# Sheet3-new.net
KiCad netlist of a schematic drawn in Altium Designer
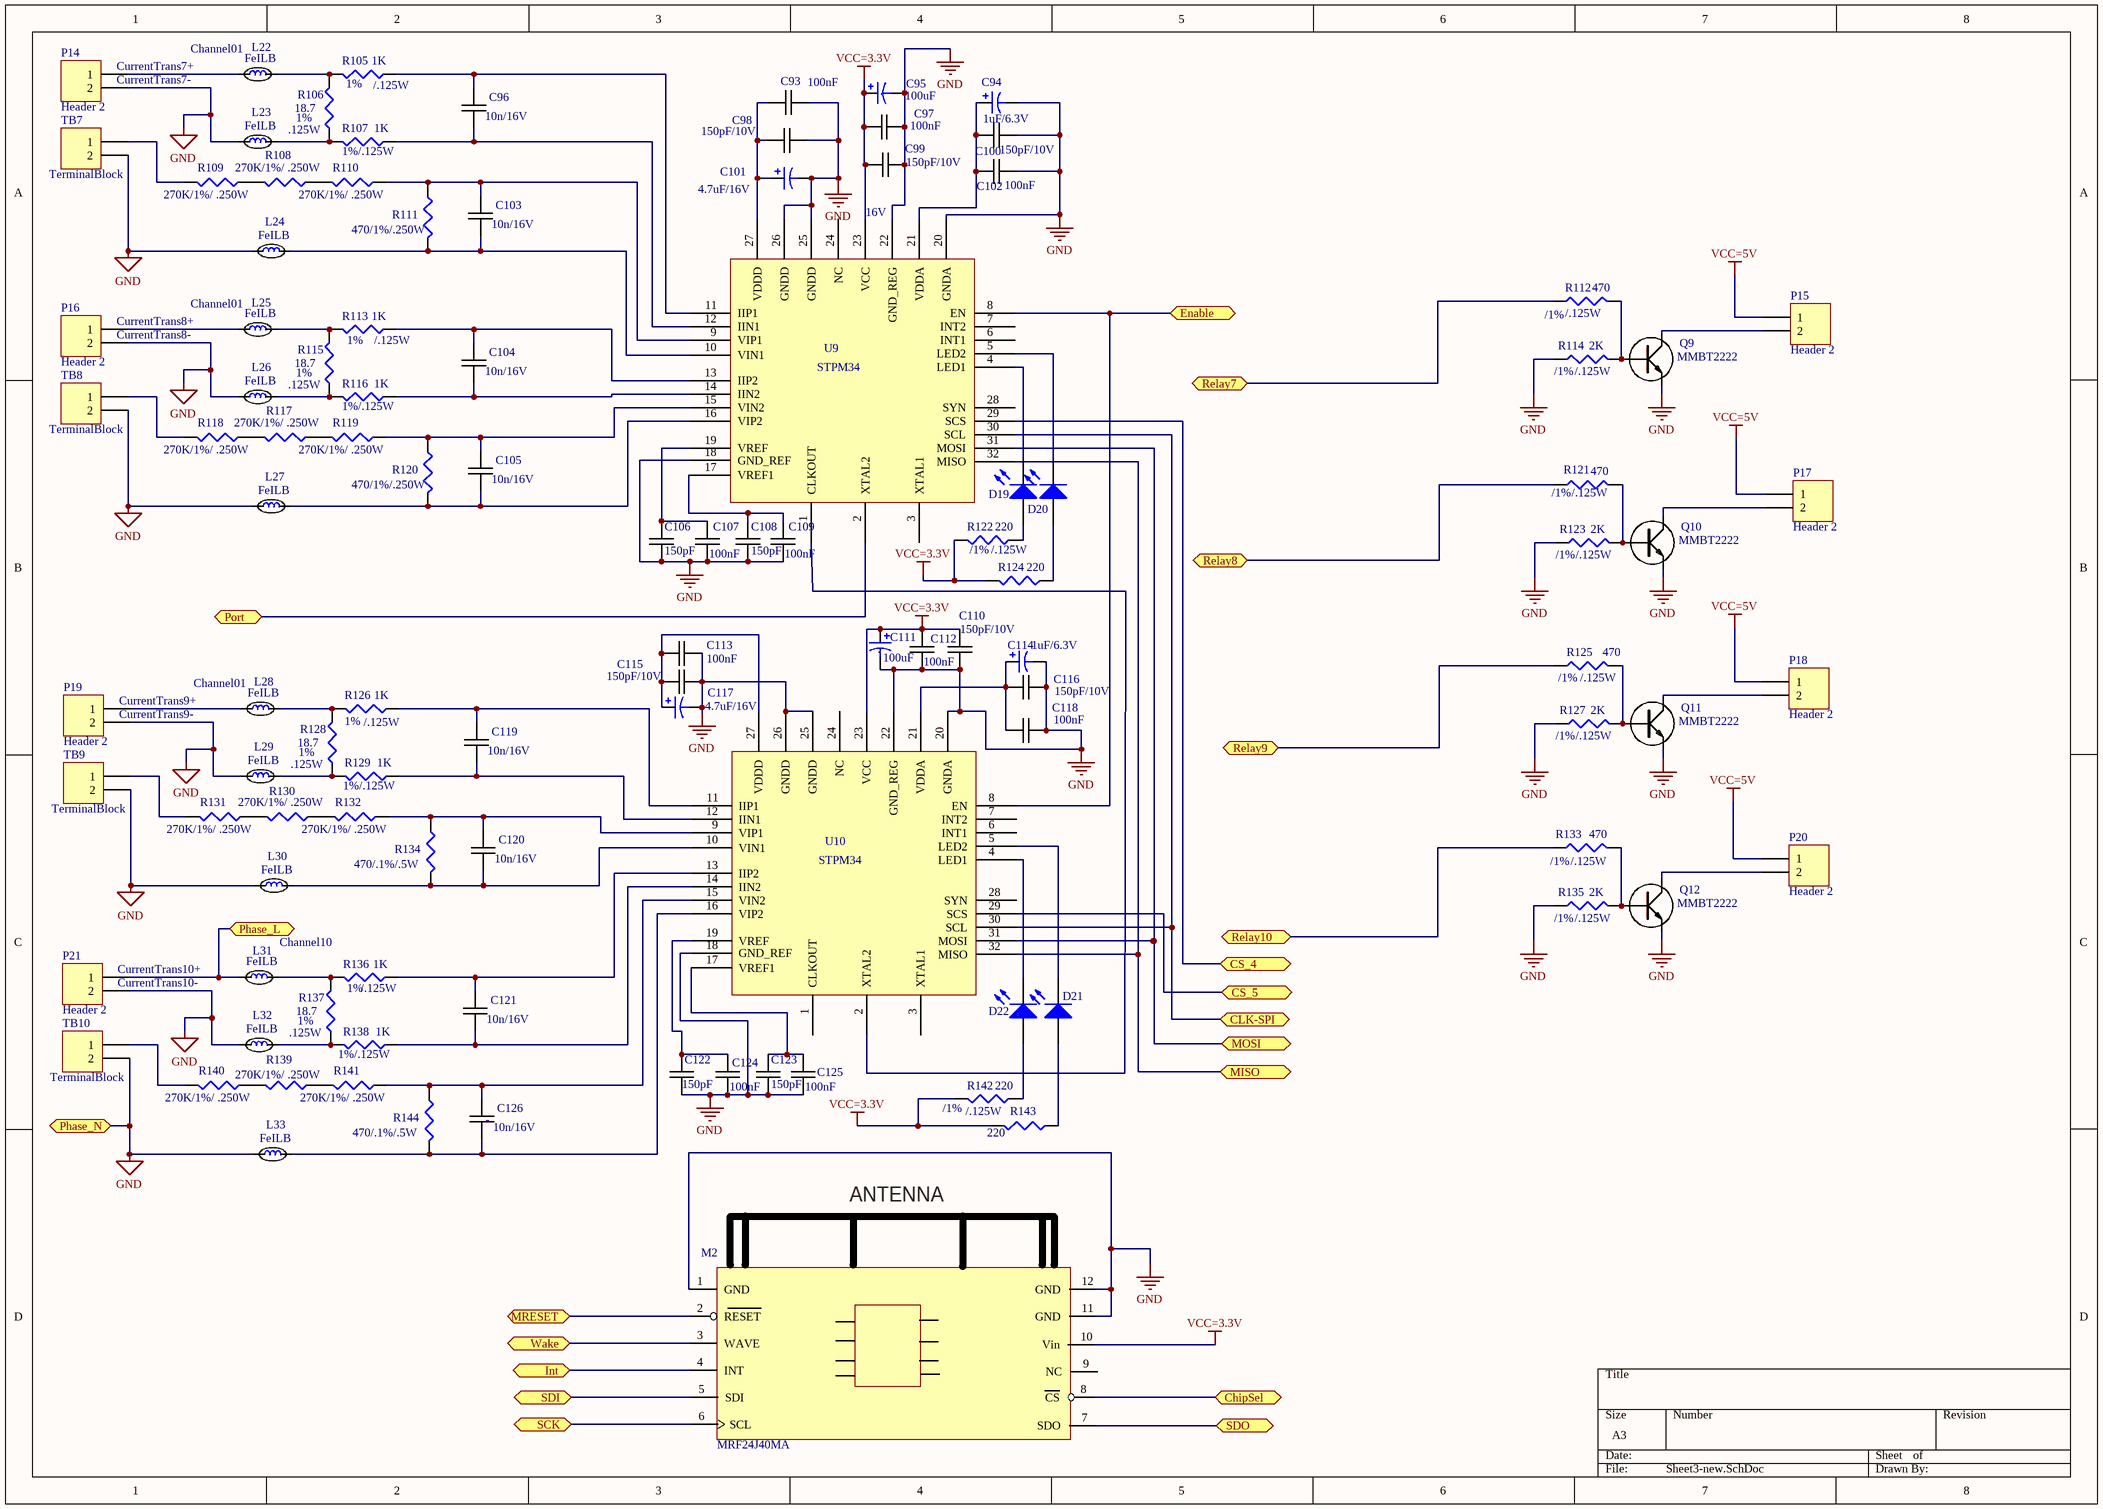
[diagram p0: Sheet3-new.SchDoc]

(export (version "E")
  (design (tool "Eeschema 10.0.6"))
  (components
    (comp (ref "C93")
      (value "100nF")
      (footprint "0402C-GENERIC")
      (description "CAPACITOR 0805 CERAMIC")
      (fields (field (name "MANUFACTURER") "Taiyo Yuden"))
      (libsource (lib "vh_altium_library") (part "0805C-18PF-50V-C0G-JOH"))
    )
    (comp (ref "C94")
      (value "1uF/6.3V")
      (footprint "0402C-GENERIC")
      (description "Polarized Capacitor (Surface Mount)")
      (fields (field (name "PUBLISHER") "Altium Limited"))
      (libsource (lib "Miscellaneous Devices") (part "Cap Pol3"))
    )
    (comp (ref "C95")
      (value "100uF")
      (footprint "100uF/10V")
      (description "Polarized Capacitor (Surface Mount)")
      (fields (field (name "MANUFACTURER") "Nichicon") (field (name "PUBLISHER") "Altium Limited"))
      (libsource (lib "Miscellaneous Devices") (part "Cap Pol3"))
    )
    (comp (ref "C96")
      (value "10n/16V")
      (footprint "0402C-GENERIC")
      (description "CAPACITOR 0805 CERAMIC")
      (fields (field (name "MANUFACTURER") "Murata Electronics"))
      (libsource (lib "vh_altium_library") (part "0805C-18PF-50V-C0G-JOH"))
    )
    (comp (ref "C97")
      (value "100nF")
      (footprint "0402C-GENERIC")
      (description "CAPACITOR 0805 CERAMIC")
      (fields (field (name "MANUFACTURER") "Taiyo Yuden"))
      (libsource (lib "vh_altium_library") (part "0805C-18PF-50V-C0G-JOH"))
    )
    (comp (ref "C98")
      (value "150pF/10V")
      (footprint "0402C-GENERIC")
      (description "CAPACITOR 0805 CERAMIC")
      (fields (field (name "MANUFACTURER") "Wurth Electronics"))
      (libsource (lib "vh_altium_library") (part "0805C-18PF-50V-C0G-JOH"))
    )
    (comp (ref "C99")
      (value "150pF/10V")
      (footprint "0402C-GENERIC")
      (description "CAPACITOR 0805 CERAMIC")
      (fields (field (name "MANUFACTURER") "Wurth Electronics"))
      (libsource (lib "vh_altium_library") (part "0805C-18PF-50V-C0G-JOH"))
    )
    (comp (ref "C100")
      (value "150pF/10V")
      (footprint "0402C-GENERIC")
      (description "CAPACITOR 0805 CERAMIC")
      (fields (field (name "MANUFACTURER") "Wurth Electronics"))
      (libsource (lib "vh_altium_library") (part "0805C-18PF-50V-C0G-JOH"))
    )
    (comp (ref "C101")
      (value "4.7uF/16V")
      (footprint "0805C-GENERIC")
      (description "Polarized Capacitor (Surface Mount)")
      (fields (field (name "MANUFACTURER") "Murata") (field (name "PUBLISHER") "Altium Limited"))
      (libsource (lib "Miscellaneous Devices") (part "Cap Pol3"))
    )
    (comp (ref "C102")
      (value "100nF")
      (footprint "0402C-GENERIC")
      (description "CAPACITOR 0805 CERAMIC")
      (fields (field (name "MANUFACTURER") "Taiyo Yuden"))
      (libsource (lib "vh_altium_library") (part "0805C-18PF-50V-C0G-JOH"))
    )
    (comp (ref "C103")
      (value "10n/16V")
      (footprint "0402C-GENERIC")
      (description "CAPACITOR 0805 CERAMIC")
      (fields (field (name "MANUFACTURER") "Murata Electronics"))
      (libsource (lib "vh_altium_library") (part "0805C-18PF-50V-C0G-JOH"))
    )
    (comp (ref "C104")
      (value "10n/16V")
      (footprint "0402C-GENERIC")
      (description "CAPACITOR 0805 CERAMIC")
      (fields (field (name "MANUFACTURER") "Murata Electronics"))
      (libsource (lib "vh_altium_library") (part "0805C-18PF-50V-C0G-JOH"))
    )
    (comp (ref "C105")
      (value "10n/16V")
      (footprint "0402C-GENERIC")
      (description "CAPACITOR 0805 CERAMIC")
      (fields (field (name "MANUFACTURER") "Murata Electronics"))
      (libsource (lib "vh_altium_library") (part "0805C-18PF-50V-C0G-JOH"))
    )
    (comp (ref "C106")
      (value "150pF")
      (footprint "0402C-GENERIC")
      (description "CAPACITOR 0805 CERAMIC")
      (fields (field (name "MANUFACTURER") "Wurth Electronics"))
      (libsource (lib "vh_altium_library") (part "0805C-18PF-50V-C0G-JOH"))
    )
    (comp (ref "C107")
      (value "100nF")
      (footprint "0402C-GENERIC")
      (description "CAPACITOR 0805 CERAMIC")
      (fields (field (name "MANUFACTURER") "Taiyo Yuden"))
      (libsource (lib "vh_altium_library") (part "0805C-18PF-50V-C0G-JOH"))
    )
    (comp (ref "C108")
      (value "150pF")
      (footprint "0402C-GENERIC")
      (description "CAPACITOR 0805 CERAMIC")
      (fields (field (name "MANUFACTURER") "Wurth Electronics"))
      (libsource (lib "vh_altium_library") (part "0805C-18PF-50V-C0G-JOH"))
    )
    (comp (ref "C109")
      (value "100nF")
      (footprint "0402C-GENERIC")
      (description "CAPACITOR 0805 CERAMIC")
      (fields (field (name "MANUFACTURER") "Taiyo Yuden"))
      (libsource (lib "vh_altium_library") (part "0805C-18PF-50V-C0G-JOH"))
    )
    (comp (ref "C110")
      (value "150pF/10V")
      (footprint "0402C-GENERIC")
      (description "CAPACITOR 0805 CERAMIC")
      (fields (field (name "MANUFACTURER") "Wurth Electronics"))
      (libsource (lib "vh_altium_library") (part "0805C-18PF-50V-C0G-JOH"))
    )
    (comp (ref "C111")
      (value "100uF")
      (footprint "100uF/10V")
      (description "Polarized Capacitor (Surface Mount)")
      (fields (field (name "MANUFACTURER") "Nichicon") (field (name "PUBLISHER") "Altium Limited"))
      (libsource (lib "Miscellaneous Devices") (part "Cap Pol3"))
    )
    (comp (ref "C112")
      (value "100nF")
      (footprint "0402C-GENERIC")
      (description "CAPACITOR 0805 CERAMIC")
      (fields (field (name "MANUFACTURER") "Taiyo Yuden"))
      (libsource (lib "vh_altium_library") (part "0805C-18PF-50V-C0G-JOH"))
    )
    (comp (ref "C113")
      (value "100nF")
      (footprint "0402C-GENERIC")
      (description "CAPACITOR 0805 CERAMIC")
      (fields (field (name "MANUFACTURER") "Taiyo Yuden"))
      (libsource (lib "vh_altium_library") (part "0805C-18PF-50V-C0G-JOH"))
    )
    (comp (ref "C114")
      (value "1uF/6.3V")
      (footprint "0402C-GENERIC")
      (description "Polarized Capacitor (Surface Mount)")
      (fields (field (name "PUBLISHER") "Altium Limited"))
      (libsource (lib "Miscellaneous Devices") (part "Cap Pol3"))
    )
    (comp (ref "C115")
      (value "150pF/10V")
      (footprint "0402C-GENERIC")
      (description "CAPACITOR 0805 CERAMIC")
      (fields (field (name "MANUFACTURER") "Wurth Electronics"))
      (libsource (lib "vh_altium_library") (part "0805C-18PF-50V-C0G-JOH"))
    )
    (comp (ref "C116")
      (value "150pF/10V")
      (footprint "0402C-GENERIC")
      (description "CAPACITOR 0805 CERAMIC")
      (fields (field (name "MANUFACTURER") "Wurth Electronics"))
      (libsource (lib "vh_altium_library") (part "0805C-18PF-50V-C0G-JOH"))
    )
    (comp (ref "C117")
      (value "4.7uF/16V")
      (footprint "0805C-GENERIC")
      (description "Polarized Capacitor (Surface Mount)")
      (fields (field (name "MANUFACTURER") "Murata") (field (name "PUBLISHER") "Altium Limited"))
      (libsource (lib "Miscellaneous Devices") (part "Cap Pol3"))
    )
    (comp (ref "C118")
      (value "100nF")
      (footprint "0402C-GENERIC")
      (description "CAPACITOR 0805 CERAMIC")
      (fields (field (name "MANUFACTURER") "Taiyo Yuden"))
      (libsource (lib "vh_altium_library") (part "0805C-18PF-50V-C0G-JOH"))
    )
    (comp (ref "C119")
      (value "10n/16V")
      (footprint "0402C-GENERIC")
      (description "CAPACITOR 0805 CERAMIC")
      (fields (field (name "MANUFACTURER") "Murata Electronics"))
      (libsource (lib "vh_altium_library") (part "0805C-18PF-50V-C0G-JOH"))
    )
    (comp (ref "C120")
      (value "10n/16V")
      (footprint "0402C-GENERIC")
      (description "CAPACITOR 0805 CERAMIC")
      (fields (field (name "MANUFACTURER") "Murata Electronics"))
      (libsource (lib "vh_altium_library") (part "0805C-18PF-50V-C0G-JOH"))
    )
    (comp (ref "C121")
      (value "10n/16V")
      (footprint "0402C-GENERIC")
      (description "CAPACITOR 0805 CERAMIC")
      (fields (field (name "MANUFACTURER") "Murata Electronics"))
      (libsource (lib "vh_altium_library") (part "0805C-18PF-50V-C0G-JOH"))
    )
    (comp (ref "C122")
      (value "150pF")
      (footprint "0402C-GENERIC")
      (description "CAPACITOR 0805 CERAMIC")
      (fields (field (name "MANUFACTURER") "Wurth Electronics"))
      (libsource (lib "vh_altium_library") (part "0805C-18PF-50V-C0G-JOH"))
    )
    (comp (ref "C123")
      (value "150pF")
      (footprint "0402C-GENERIC")
      (description "CAPACITOR 0805 CERAMIC")
      (fields (field (name "MANUFACTURER") "Wurth Electronics"))
      (libsource (lib "vh_altium_library") (part "0805C-18PF-50V-C0G-JOH"))
    )
    (comp (ref "C124")
      (value "100nF")
      (footprint "0402C-GENERIC")
      (description "CAPACITOR 0805 CERAMIC")
      (fields (field (name "MANUFACTURER") "Taiyo Yuden"))
      (libsource (lib "vh_altium_library") (part "0805C-18PF-50V-C0G-JOH"))
    )
    (comp (ref "C125")
      (value "100nF")
      (footprint "0402C-GENERIC")
      (description "CAPACITOR 0805 CERAMIC")
      (fields (field (name "MANUFACTURER") "Taiyo Yuden"))
      (libsource (lib "vh_altium_library") (part "0805C-18PF-50V-C0G-JOH"))
    )
    (comp (ref "C126")
      (value "10n/16V")
      (footprint "0402C-GENERIC")
      (description "CAPACITOR 0805 CERAMIC")
      (fields (field (name "MANUFACTURER") "Murata Electronics"))
      (libsource (lib "vh_altium_library") (part "0805C-18PF-50V-C0G-JOH"))
    )
    (comp (ref "D19")
      (value "LED2")
      (footprint "LED-SM")
      (description "Typical RED, GREEN, YELLOW, AMBER GaAs LED")
      (fields (field (name "MANUFACTURER") "Lite-On Inc") (field (name "PUBLISHER") "Altium Limited"))
      (libsource (lib "Miscellaneous Devices") (part "LED2"))
    )
    (comp (ref "D20")
      (value "LED2")
      (footprint "LED-SM")
      (description "Typical RED, GREEN, YELLOW, AMBER GaAs LED")
      (fields (field (name "MANUFACTURER") "Lite-On Inc") (field (name "PUBLISHER") "Altium Limited"))
      (libsource (lib "Miscellaneous Devices") (part "LED2"))
    )
    (comp (ref "D21")
      (value "LED2")
      (footprint "LED-SM")
      (description "Typical RED, GREEN, YELLOW, AMBER GaAs LED")
      (fields (field (name "MANUFACTURER") "Lite-On Inc") (field (name "PUBLISHER") "Altium Limited"))
      (libsource (lib "Miscellaneous Devices") (part "LED2"))
    )
    (comp (ref "D22")
      (value "LED2")
      (footprint "LED-SM")
      (description "Typical RED, GREEN, YELLOW, AMBER GaAs LED")
      (fields (field (name "MANUFACTURER") "Lite-On Inc") (field (name "PUBLISHER") "Altium Limited"))
      (libsource (lib "Miscellaneous Devices") (part "LED2"))
    )
    (comp (ref "L22")
      (value "FeILB")
      (footprint "0603C-TBD")
      (fields (field (name "MANUFACTURER") "Brand Samsung"))
      (libsource (lib "SMLib") (part "FerrBeads/ILBB"))
    )
    (comp (ref "L23")
      (value "FeILB")
      (footprint "0603C-TBD")
      (fields (field (name "MANUFACTURER") "Brand Samsung"))
      (libsource (lib "SMLib") (part "FerrBeads/ILBB"))
    )
    (comp (ref "L24")
      (value "FeILB")
      (footprint "0603C-TBD")
      (fields (field (name "MANUFACTURER") "Brand Samsung"))
      (libsource (lib "SMLib") (part "FerrBeads/ILBB"))
    )
    (comp (ref "L25")
      (value "FeILB")
      (footprint "0603C-TBD")
      (fields (field (name "MANUFACTURER") "Brand Samsung"))
      (libsource (lib "SMLib") (part "FerrBeads/ILBB"))
    )
    (comp (ref "L26")
      (value "FeILB")
      (footprint "0603C-TBD")
      (fields (field (name "MANUFACTURER") "Brand Samsung"))
      (libsource (lib "SMLib") (part "FerrBeads/ILBB"))
    )
    (comp (ref "L27")
      (value "FeILB")
      (footprint "0603C-TBD")
      (fields (field (name "MANUFACTURER") "Brand Samsung"))
      (libsource (lib "SMLib") (part "FerrBeads/ILBB"))
    )
    (comp (ref "L28")
      (value "FeILB")
      (footprint "0603C-TBD")
      (fields (field (name "MANUFACTURER") "Brand Samsung"))
      (libsource (lib "SMLib") (part "FerrBeads/ILBB"))
    )
    (comp (ref "L29")
      (value "FeILB")
      (footprint "0603C-TBD")
      (fields (field (name "MANUFACTURER") "Brand Samsung"))
      (libsource (lib "SMLib") (part "FerrBeads/ILBB"))
    )
    (comp (ref "L30")
      (value "FeILB")
      (footprint "0603C-TBD")
      (fields (field (name "MANUFACTURER") "Brand Samsung"))
      (libsource (lib "SMLib") (part "FerrBeads/ILBB"))
    )
    (comp (ref "L31")
      (value "FeILB")
      (footprint "0603C-TBD")
      (fields (field (name "MANUFACTURER") "Brand Samsung"))
      (libsource (lib "SMLib") (part "FerrBeads/ILBB"))
    )
    (comp (ref "L32")
      (value "FeILB")
      (footprint "0603C-TBD")
      (fields (field (name "MANUFACTURER") "Brand Samsung"))
      (libsource (lib "SMLib") (part "FerrBeads/ILBB"))
    )
    (comp (ref "L33")
      (value "FeILB")
      (footprint "0603C-TBD")
      (fields (field (name "MANUFACTURER") "Brand Samsung"))
      (libsource (lib "SMLib") (part "FerrBeads/ILBB"))
    )
    (comp (ref "M2")
      (value "MRF24J40MA")
      (footprint "MRF24J40MA-zigBEE module")
      (fields (field (name "MANUFACTURER") "Microchip"))
      (libsource (lib "SMLib") (part "MRF24J40MA"))
    )
    (comp (ref "P14")
      (value "Header 2")
      (footprint "BG090-header")
      (description "Header, 2-Pin")
      (fields
        (field (name "MANUFACTURER") "Clobal Connector technology Ltd")
        (field (name "PUBLISHER") "Altium Limited")
      )
      (libsource (lib "Miscellaneous Connectors") (part "Header 2"))
    )
    (comp (ref "P15")
      (value "Header 2")
      (footprint "BG090-header")
      (description "Header, 2-Pin")
      (fields
        (field (name "MANUFACTURER") "Clobal Connector technology Ltd")
        (field (name "PUBLISHER") "Altium Limited")
      )
      (libsource (lib "") (part "Header 2_1"))
    )
    (comp (ref "P16")
      (value "Header 2")
      (footprint "BG090-header")
      (description "Header, 2-Pin")
      (fields
        (field (name "MANUFACTURER") "Clobal Connector technology Ltd")
        (field (name "PUBLISHER") "Altium Limited")
      )
      (libsource (lib "Miscellaneous Connectors") (part "Header 2"))
    )
    (comp (ref "P17")
      (value "Header 2")
      (footprint "BG090-header")
      (description "Header, 2-Pin")
      (fields
        (field (name "MANUFACTURER") "Clobal Connector technology Ltd")
        (field (name "PUBLISHER") "Altium Limited")
      )
      (libsource (lib "") (part "Header 2_1"))
    )
    (comp (ref "P18")
      (value "Header 2")
      (footprint "BG090-header")
      (description "Header, 2-Pin")
      (fields
        (field (name "MANUFACTURER") "Clobal Connector technology Ltd")
        (field (name "PUBLISHER") "Altium Limited")
      )
      (libsource (lib "") (part "Header 2_1"))
    )
    (comp (ref "P19")
      (value "Header 2")
      (footprint "BG090-header")
      (description "Header, 2-Pin")
      (fields
        (field (name "MANUFACTURER") "Clobal Connector technology Ltd")
        (field (name "PUBLISHER") "Altium Limited")
      )
      (libsource (lib "Miscellaneous Connectors") (part "Header 2"))
    )
    (comp (ref "P20")
      (value "Header 2")
      (footprint "BG090-header")
      (description "Header, 2-Pin")
      (fields
        (field (name "MANUFACTURER") "Clobal Connector technology Ltd")
        (field (name "PUBLISHER") "Altium Limited")
      )
      (libsource (lib "") (part "Header 2_1"))
    )
    (comp (ref "P21")
      (value "Header 2")
      (footprint "BG090-header")
      (description "Header, 2-Pin")
      (fields
        (field (name "MANUFACTURER") "Clobal Connector technology Ltd")
        (field (name "PUBLISHER") "Altium Limited")
      )
      (libsource (lib "Miscellaneous Connectors") (part "Header 2"))
    )
    (comp (ref "Q9")
      (value "MMBT2222")
      (footprint "MMBT2222")
      (description "BC847 SMALL SIGNAL NPN TRANSISTOR")
      (fields (field (name "MANUFACTURER") "Diodes  Inc."))
      (libsource (lib "vh_altium_library") (part "MMBT2222"))
    )
    (comp (ref "Q10")
      (value "MMBT2222")
      (footprint "MMBT2222")
      (description "BC847 SMALL SIGNAL NPN TRANSISTOR")
      (fields (field (name "MANUFACTURER") "Diodes  Inc."))
      (libsource (lib "vh_altium_library") (part "MMBT2222"))
    )
    (comp (ref "Q11")
      (value "MMBT2222")
      (footprint "MMBT2222")
      (description "BC847 SMALL SIGNAL NPN TRANSISTOR")
      (fields (field (name "MANUFACTURER") "Diodes  Inc."))
      (libsource (lib "vh_altium_library") (part "MMBT2222"))
    )
    (comp (ref "Q12")
      (value "MMBT2222")
      (footprint "MMBT2222")
      (description "BC847 SMALL SIGNAL NPN TRANSISTOR")
      (fields (field (name "MANUFACTURER") "Diodes  Inc."))
      (libsource (lib "vh_altium_library") (part "MMBT2222"))
    )
    (comp (ref "R105")
      (value "1K")
      (footprint "0805C-GENERIC")
      (description "Resistor")
      (fields
        (field (name "MANUFACTURER") "StackpoleElectronics")
        (field (name "PUBLISHER") "Altium Limited")
      )
      (libsource (lib "Miscellaneous Devices") (part "Res3"))
    )
    (comp (ref "R106")
      (value "18.7")
      (footprint "vh_altium_library:0805R-10")
      (description "Resistor")
      (fields (field (name "MANUFACTURER") "Vishay Pale") (field (name "PUBLISHER") "Altium Limited"))
      (libsource (lib "Miscellaneous Devices") (part "Res3"))
    )
    (comp (ref "R107")
      (value "1K")
      (footprint "0805C-GENERIC")
      (description "Resistor")
      (fields
        (field (name "MANUFACTURER") "StackpoleElectronics")
        (field (name "PUBLISHER") "Altium Limited")
      )
      (libsource (lib "Miscellaneous Devices") (part "Res3"))
    )
    (comp (ref "R108")
      (value "270K/1%/ .250W")
      (footprint "generic:1210R-GENERIC")
      (description "Resistor")
      (fields (field (name "MANUFACTURER") "Panasonic  Co") (field (name "PUBLISHER") "Altium Limited"))
      (libsource (lib "Miscellaneous Devices") (part "Res3"))
    )
    (comp (ref "R109")
      (value "270K/1%/ .250W")
      (footprint "generic:1210R-GENERIC")
      (description "Resistor")
      (fields (field (name "MANUFACTURER") "Panasonic  Co") (field (name "PUBLISHER") "Altium Limited"))
      (libsource (lib "Miscellaneous Devices") (part "Res3"))
    )
    (comp (ref "R110")
      (value "270K/1%/ .250W")
      (footprint "generic:1210R-GENERIC")
      (description "Resistor")
      (fields (field (name "MANUFACTURER") "Panasonic  Co") (field (name "PUBLISHER") "Altium Limited"))
      (libsource (lib "Miscellaneous Devices") (part "Res3"))
    )
    (comp (ref "R111")
      (value "470/1%/.250W")
      (footprint "1206FB-GENERIC")
      (description "Resistor")
      (fields (field (name "MANUFACTURER") "Panasonic Co") (field (name "PUBLISHER") "Altium Limited"))
      (libsource (lib "Miscellaneous Devices") (part "Res3"))
    )
    (comp (ref "R112")
      (value "470")
      (footprint "vh_altium_library:0805R-39")
      (description "Resistor")
      (fields
        (field (name "MANUFACTURER") "Stackpole electronics")
        (field (name "PUBLISHER") "Altium Limited")
      )
      (libsource (lib "Miscellaneous Devices") (part "Res3"))
    )
    (comp (ref "R113")
      (value "1K")
      (footprint "0805C-GENERIC")
      (description "Resistor")
      (fields
        (field (name "MANUFACTURER") "StackpoleElectronics")
        (field (name "PUBLISHER") "Altium Limited")
      )
      (libsource (lib "Miscellaneous Devices") (part "Res3"))
    )
    (comp (ref "R114")
      (value "2K")
      (footprint "vh_altium_library:0805R-180")
      (description "Resistor")
      (fields
        (field (name "MANUFACTURER") "Stackpole Electronics")
        (field (name "PUBLISHER") "Altium Limited")
      )
      (libsource (lib "Miscellaneous Devices") (part "Res3"))
    )
    (comp (ref "R115")
      (value "18.7")
      (footprint "vh_altium_library:0805R-10")
      (description "Resistor")
      (fields (field (name "MANUFACTURER") "Vishay Pale") (field (name "PUBLISHER") "Altium Limited"))
      (libsource (lib "Miscellaneous Devices") (part "Res3"))
    )
    (comp (ref "R116")
      (value "1K")
      (footprint "0805C-GENERIC")
      (description "Resistor")
      (fields
        (field (name "MANUFACTURER") "StackpoleElectronics")
        (field (name "PUBLISHER") "Altium Limited")
      )
      (libsource (lib "Miscellaneous Devices") (part "Res3"))
    )
    (comp (ref "R117")
      (value "270K/1%/ .250W")
      (footprint "generic:1210R-GENERIC")
      (description "Resistor")
      (fields (field (name "MANUFACTURER") "Panasonic  Co") (field (name "PUBLISHER") "Altium Limited"))
      (libsource (lib "Miscellaneous Devices") (part "Res3"))
    )
    (comp (ref "R118")
      (value "270K/1%/ .250W")
      (footprint "generic:1210R-GENERIC")
      (description "Resistor")
      (fields (field (name "MANUFACTURER") "Panasonic  Co") (field (name "PUBLISHER") "Altium Limited"))
      (libsource (lib "Miscellaneous Devices") (part "Res3"))
    )
    (comp (ref "R119")
      (value "270K/1%/ .250W")
      (footprint "generic:1210R-GENERIC")
      (description "Resistor")
      (fields (field (name "MANUFACTURER") "Panasonic  Co") (field (name "PUBLISHER") "Altium Limited"))
      (libsource (lib "Miscellaneous Devices") (part "Res3"))
    )
    (comp (ref "R120")
      (value "470/1%/.250W")
      (footprint "1206FB-GENERIC")
      (description "Resistor")
      (fields (field (name "MANUFACTURER") "Panasonic Co") (field (name "PUBLISHER") "Altium Limited"))
      (libsource (lib "Miscellaneous Devices") (part "Res3"))
    )
    (comp (ref "R121")
      (value "470")
      (footprint "vh_altium_library:0805R-39")
      (description "Resistor")
      (fields
        (field (name "MANUFACTURER") "Stackpole electronics")
        (field (name "PUBLISHER") "Altium Limited")
      )
      (libsource (lib "Miscellaneous Devices") (part "Res3"))
    )
    (comp (ref "R122")
      (value "220")
      (footprint "0805C-GENERIC")
      (description "Resistor")
      (fields
        (field (name "MANUFACTURER") "Stackpole Electronics")
        (field (name "PUBLISHER") "Altium Limited")
      )
      (libsource (lib "Miscellaneous Devices") (part "Res3"))
    )
    (comp (ref "R123")
      (value "2K")
      (footprint "vh_altium_library:0805R-180")
      (description "Resistor")
      (fields
        (field (name "MANUFACTURER") "Stackpole Electronics")
        (field (name "PUBLISHER") "Altium Limited")
      )
      (libsource (lib "Miscellaneous Devices") (part "Res3"))
    )
    (comp (ref "R124")
      (value "220")
      (footprint "0805C-GENERIC")
      (description "Resistor")
      (fields
        (field (name "MANUFACTURER") "Stackpole Electronics")
        (field (name "PUBLISHER") "Altium Limited")
      )
      (libsource (lib "Miscellaneous Devices") (part "Res3"))
    )
    (comp (ref "R125")
      (value "470")
      (footprint "vh_altium_library:0805R-39")
      (description "Resistor")
      (fields
        (field (name "MANUFACTURER") "Stackpole electronics")
        (field (name "PUBLISHER") "Altium Limited")
      )
      (libsource (lib "Miscellaneous Devices") (part "Res3"))
    )
    (comp (ref "R126")
      (value "1K")
      (footprint "0805C-GENERIC")
      (description "Resistor")
      (fields
        (field (name "MANUFACTURER") "StackpoleElectronics")
        (field (name "PUBLISHER") "Altium Limited")
      )
      (libsource (lib "Miscellaneous Devices") (part "Res3"))
    )
    (comp (ref "R127")
      (value "2K")
      (footprint "vh_altium_library:0805R-180")
      (description "Resistor")
      (fields
        (field (name "MANUFACTURER") "Stackpole Electronics")
        (field (name "PUBLISHER") "Altium Limited")
      )
      (libsource (lib "Miscellaneous Devices") (part "Res3"))
    )
    (comp (ref "R128")
      (value "18.7")
      (footprint "vh_altium_library:0805R-10")
      (description "Resistor")
      (fields (field (name "MANUFACTURER") "Vishay Pale") (field (name "PUBLISHER") "Altium Limited"))
      (libsource (lib "Miscellaneous Devices") (part "Res3"))
    )
    (comp (ref "R129")
      (value "1K")
      (footprint "0805C-GENERIC")
      (description "Resistor")
      (fields
        (field (name "MANUFACTURER") "StackpoleElectronics")
        (field (name "PUBLISHER") "Altium Limited")
      )
      (libsource (lib "Miscellaneous Devices") (part "Res3"))
    )
    (comp (ref "R130")
      (value "270K/1%/ .250W")
      (footprint "generic:1210R-GENERIC")
      (description "Resistor")
      (fields (field (name "MANUFACTURER") "Panasonic  Co") (field (name "PUBLISHER") "Altium Limited"))
      (libsource (lib "Miscellaneous Devices") (part "Res3"))
    )
    (comp (ref "R131")
      (value "270K/1%/ .250W")
      (footprint "generic:1210R-GENERIC")
      (description "Resistor")
      (fields (field (name "MANUFACTURER") "Panasonic  Co") (field (name "PUBLISHER") "Altium Limited"))
      (libsource (lib "Miscellaneous Devices") (part "Res3"))
    )
    (comp (ref "R132")
      (value "270K/1%/ .250W")
      (footprint "generic:1210R-GENERIC")
      (description "Resistor")
      (fields (field (name "MANUFACTURER") "Panasonic  Co") (field (name "PUBLISHER") "Altium Limited"))
      (libsource (lib "Miscellaneous Devices") (part "Res3"))
    )
    (comp (ref "R133")
      (value "470")
      (footprint "vh_altium_library:0805R-39")
      (description "Resistor")
      (fields
        (field (name "MANUFACTURER") "Stackpole electronics")
        (field (name "PUBLISHER") "Altium Limited")
      )
      (libsource (lib "Miscellaneous Devices") (part "Res3"))
    )
    (comp (ref "R134")
      (value "470/.1%/.5W")
      (footprint "1210C-GENERIC")
      (description "Resistor")
      (fields (field (name "MANUFACTURER") "Panasonic Co") (field (name "PUBLISHER") "Altium Limited"))
      (libsource (lib "Miscellaneous Devices") (part "Res3"))
    )
    (comp (ref "R135")
      (value "2K")
      (footprint "vh_altium_library:0805R-180")
      (description "Resistor")
      (fields
        (field (name "MANUFACTURER") "Stackpole Electronics")
        (field (name "PUBLISHER") "Altium Limited")
      )
      (libsource (lib "Miscellaneous Devices") (part "Res3"))
    )
    (comp (ref "R136")
      (value "1K")
      (footprint "0805C-GENERIC")
      (description "Resistor")
      (fields
        (field (name "MANUFACTURER") "StackpoleElectronics")
        (field (name "PUBLISHER") "Altium Limited")
      )
      (libsource (lib "Miscellaneous Devices") (part "Res3"))
    )
    (comp (ref "R137")
      (value "18.7")
      (footprint "vh_altium_library:0805R-10")
      (description "Resistor")
      (fields (field (name "MANUFACTURER") "Vishay Pale") (field (name "PUBLISHER") "Altium Limited"))
      (libsource (lib "Miscellaneous Devices") (part "Res3"))
    )
    (comp (ref "R138")
      (value "1K")
      (footprint "0805C-GENERIC")
      (description "Resistor")
      (fields
        (field (name "MANUFACTURER") "StackpoleElectronics")
        (field (name "PUBLISHER") "Altium Limited")
      )
      (libsource (lib "Miscellaneous Devices") (part "Res3"))
    )
    (comp (ref "R139")
      (value "270K/1%/ .250W")
      (footprint "generic:1210R-GENERIC")
      (description "Resistor")
      (fields (field (name "MANUFACTURER") "Panasonic  Co") (field (name "PUBLISHER") "Altium Limited"))
      (libsource (lib "Miscellaneous Devices") (part "Res3"))
    )
    (comp (ref "R140")
      (value "270K/1%/ .250W")
      (footprint "generic:1210R-GENERIC")
      (description "Resistor")
      (fields (field (name "MANUFACTURER") "Panasonic  Co") (field (name "PUBLISHER") "Altium Limited"))
      (libsource (lib "Miscellaneous Devices") (part "Res3"))
    )
    (comp (ref "R141")
      (value "270K/1%/ .250W")
      (footprint "generic:1210R-GENERIC")
      (description "Resistor")
      (fields (field (name "MANUFACTURER") "Panasonic  Co") (field (name "PUBLISHER") "Altium Limited"))
      (libsource (lib "Miscellaneous Devices") (part "Res3"))
    )
    (comp (ref "R142")
      (value "220")
      (footprint "0805C-GENERIC")
      (description "Resistor")
      (fields
        (field (name "MANUFACTURER") "Stackpole Electronics")
        (field (name "PUBLISHER") "Altium Limited")
      )
      (libsource (lib "Miscellaneous Devices") (part "Res3"))
    )
    (comp (ref "R143")
      (value "220")
      (footprint "0805C-GENERIC")
      (description "Resistor")
      (fields
        (field (name "MANUFACTURER") "Stackpole Electronics")
        (field (name "PUBLISHER") "Altium Limited")
      )
      (libsource (lib "Miscellaneous Devices") (part "Res3"))
    )
    (comp (ref "R144")
      (value "470/.1%/.5W")
      (footprint "1210C-GENERIC")
      (description "Resistor")
      (fields (field (name "MANUFACTURER") "Panasonic Co") (field (name "PUBLISHER") "Altium Limited"))
      (libsource (lib "Miscellaneous Devices") (part "Res3"))
    )
    (comp (ref "TB7")
      (value "TerminalBlock")
      (footprint "Terminal Block 2x5mm")
      (description "Header, 2-Pin")
      (fields (field (name "PUBLISHER") "Altium Limited"))
      (libsource (lib "Miscellaneous Connectors") (part "Header 2"))
    )
    (comp (ref "TB8")
      (value "TerminalBlock")
      (footprint "Terminal Block 2x5mm")
      (description "Header, 2-Pin")
      (fields (field (name "PUBLISHER") "Altium Limited"))
      (libsource (lib "Miscellaneous Connectors") (part "Header 2"))
    )
    (comp (ref "TB9")
      (value "TerminalBlock")
      (footprint "Terminal Block 2x5mm")
      (description "Header, 2-Pin")
      (fields (field (name "PUBLISHER") "Altium Limited"))
      (libsource (lib "Miscellaneous Connectors") (part "Header 2"))
    )
    (comp (ref "TB10")
      (value "TerminalBlock")
      (footprint "Terminal Block 2x5mm")
      (description "Header, 2-Pin")
      (fields (field (name "PUBLISHER") "Altium Limited"))
      (libsource (lib "Miscellaneous Connectors") (part "Header 2"))
    )
    (comp (ref "U9")
      (value "STPM34")
      (footprint "32M1-A_L")
      (fields (field (name "MANUFACTURER") "STMicroelectronic"))
      (libsource (lib "SMLib") (part "STPM34"))
    )
    (comp (ref "U10")
      (value "STPM34")
      (footprint "32M1-A_L")
      (fields (field (name "MANUFACTURER") "STMicroelectronic"))
      (libsource (lib "SMLib") (part "STPM34"))
    )
  )
  (nets
    (net (code "1") (name "/CLK-SPI") (class "Default")
      (node (ref "U10") (pin "30") (pinfunction "SCL_30") (pintype "passive"))
      (node (ref "U9") (pin "30") (pinfunction "SCL_30") (pintype "passive"))
    )
    (net (code "2") (name "/CS_4") (class "Default")
      (node (ref "U9") (pin "29") (pinfunction "SCS_29") (pintype "passive"))
    )
    (net (code "3") (name "/CS_5") (class "Default")
      (node (ref "U10") (pin "29") (pinfunction "SCS_29") (pintype "passive"))
    )
    (net (code "4") (name "/ChipSel") (class "Default")
      (node (ref "M2") (pin "8") (pinfunction "CS_8") (pintype "passive"))
    )
    (net (code "5") (name "/Enable") (class "Default")
      (node (ref "U10") (pin "8") (pinfunction "EN_8") (pintype "passive"))
      (node (ref "U9") (pin "8") (pinfunction "EN_8") (pintype "passive"))
    )
    (net (code "6") (name "/Int") (class "Default")
      (node (ref "M2") (pin "4") (pinfunction "INT_4") (pintype "passive"))
    )
    (net (code "7") (name "/MISO") (class "Default")
      (node (ref "U10") (pin "32") (pinfunction "MISO_32") (pintype "passive"))
      (node (ref "U9") (pin "32") (pinfunction "MISO_32") (pintype "passive"))
    )
    (net (code "8") (name "/MOSI") (class "Default")
      (node (ref "U10") (pin "31") (pinfunction "MOSI_31") (pintype "passive"))
      (node (ref "U9") (pin "31") (pinfunction "MOSI_31") (pintype "passive"))
    )
    (net (code "9") (name "/MRESET") (class "Default")
      (node (ref "M2") (pin "2") (pinfunction "RESET_2") (pintype "passive"))
    )
    (net (code "10") (name "/Phase_L") (class "Default")
      (node (ref "L31") (pin "1") (pinfunction "1_1") (pintype "passive"))
      (node (ref "P21") (pin "1") (pinfunction "1_1") (pintype "passive"))
    )
    (net (code "11") (name "/Port") (class "Default")
      (node (ref "U9") (pin "2") (pinfunction "XTAL2_2") (pintype "passive"))
    )
    (net (code "12") (name "/Relay7") (class "Default")
      (node (ref "R112") (pin "1") (pinfunction "1_1") (pintype "passive"))
    )
    (net (code "13") (name "/Relay8") (class "Default")
      (node (ref "R121") (pin "1") (pinfunction "1_1") (pintype "passive"))
    )
    (net (code "14") (name "/Relay9") (class "Default")
      (node (ref "R125") (pin "1") (pinfunction "1_1") (pintype "passive"))
    )
    (net (code "15") (name "/Relay10") (class "Default")
      (node (ref "R133") (pin "1") (pinfunction "1_1") (pintype "passive"))
    )
    (net (code "16") (name "/SCK") (class "Default")
      (node (ref "M2") (pin "6") (pinfunction "SCL_6") (pintype "passive"))
    )
    (net (code "17") (name "/SDI") (class "Default")
      (node (ref "M2") (pin "5") (pinfunction "SDI_5") (pintype "passive"))
    )
    (net (code "18") (name "/SDO") (class "Default")
      (node (ref "M2") (pin "7") (pinfunction "SDO_7") (pintype "passive"))
    )
    (net (code "19") (name "/Wake") (class "Default")
      (node (ref "M2") (pin "3") (pinfunction "WAVE_3") (pintype "passive"))
    )
    (net (code "20") (name "GND") (class "Default")
      (node (ref "C100") (pin "1") (pintype "passive"))
      (node (ref "C101") (pin "2") (pinfunction "2_2") (pintype "passive"))
      (node (ref "C102") (pin "2") (pintype "passive"))
      (node (ref "C106") (pin "2") (pintype "passive"))
      (node (ref "C107") (pin "2") (pintype "passive"))
      (node (ref "C108") (pin "2") (pintype "passive"))
      (node (ref "C109") (pin "2") (pintype "passive"))
      (node (ref "C110") (pin "2") (pintype "passive"))
      (node (ref "C111") (pin "2") (pinfunction "2_2") (pintype "passive"))
      (node (ref "C112") (pin "2") (pintype "passive"))
      (node (ref "C113") (pin "2") (pintype "passive"))
      (node (ref "C114") (pin "2") (pinfunction "2_2") (pintype "passive"))
      (node (ref "C115") (pin "2") (pintype "passive"))
      (node (ref "C116") (pin "2") (pintype "passive"))
      (node (ref "C117") (pin "2") (pinfunction "2_2") (pintype "passive"))
      (node (ref "C118") (pin "2") (pintype "passive"))
      (node (ref "C122") (pin "2") (pintype "passive"))
      (node (ref "C123") (pin "2") (pintype "passive"))
      (node (ref "C124") (pin "2") (pintype "passive"))
      (node (ref "C125") (pin "2") (pintype "passive"))
      (node (ref "C93") (pin "2") (pintype "passive"))
      (node (ref "C94") (pin "2") (pinfunction "2_2") (pintype "passive"))
      (node (ref "C95") (pin "2") (pinfunction "2_2") (pintype "passive"))
      (node (ref "C97") (pin "2") (pintype "passive"))
      (node (ref "C98") (pin "2") (pintype "passive"))
      (node (ref "C99") (pin "2") (pintype "passive"))
      (node (ref "L23") (pin "1") (pinfunction "1_1") (pintype "passive"))
      (node (ref "L24") (pin "1") (pinfunction "1_1") (pintype "passive"))
      (node (ref "L26") (pin "1") (pinfunction "1_1") (pintype "passive"))
      (node (ref "L27") (pin "1") (pinfunction "1_1") (pintype "passive"))
      (node (ref "L29") (pin "1") (pinfunction "1_1") (pintype "passive"))
      (node (ref "L30") (pin "1") (pinfunction "1_1") (pintype "passive"))
      (node (ref "L32") (pin "1") (pinfunction "1_1") (pintype "passive"))
      (node (ref "L33") (pin "1") (pinfunction "1_1") (pintype "passive"))
      (node (ref "M2") (pin "1") (pinfunction "GND_1") (pintype "passive"))
      (node (ref "M2") (pin "11") (pinfunction "GND_11") (pintype "passive"))
      (node (ref "M2") (pin "12") (pinfunction "GND_12") (pintype "passive"))
      (node (ref "P14") (pin "2") (pinfunction "2_2") (pintype "passive"))
      (node (ref "P16") (pin "2") (pinfunction "2_2") (pintype "passive"))
      (node (ref "P19") (pin "2") (pinfunction "2_2") (pintype "passive"))
      (node (ref "P21") (pin "2") (pinfunction "2_2") (pintype "passive"))
      (node (ref "Q10") (pin "E") (pintype "passive"))
      (node (ref "Q11") (pin "E") (pintype "passive"))
      (node (ref "Q12") (pin "E") (pintype "passive"))
      (node (ref "Q9") (pin "E") (pintype "passive"))
      (node (ref "R114") (pin "1") (pinfunction "1_1") (pintype "passive"))
      (node (ref "R123") (pin "1") (pinfunction "1_1") (pintype "passive"))
      (node (ref "R127") (pin "1") (pinfunction "1_1") (pintype "passive"))
      (node (ref "R135") (pin "1") (pinfunction "1_1") (pintype "passive"))
      (node (ref "TB10") (pin "2") (pinfunction "2_2") (pintype "passive"))
      (node (ref "TB7") (pin "2") (pinfunction "2_2") (pintype "passive"))
      (node (ref "TB8") (pin "2") (pinfunction "2_2") (pintype "passive"))
      (node (ref "TB9") (pin "2") (pinfunction "2_2") (pintype "passive"))
      (node (ref "U10") (pin "18") (pinfunction "GND_REF_18") (pintype "passive"))
      (node (ref "U10") (pin "20") (pinfunction "GNDA_20") (pintype "passive"))
      (node (ref "U10") (pin "22") (pinfunction "GND_REG_22") (pintype "passive"))
      (node (ref "U10") (pin "25") (pinfunction "GNDD_25") (pintype "passive"))
      (node (ref "U10") (pin "26") (pinfunction "GNDD_26") (pintype "passive"))
      (node (ref "U9") (pin "18") (pinfunction "GND_REF_18") (pintype "passive"))
      (node (ref "U9") (pin "20") (pinfunction "GNDA_20") (pintype "passive"))
      (node (ref "U9") (pin "22") (pinfunction "GND_REG_22") (pintype "passive"))
      (node (ref "U9") (pin "25") (pinfunction "GNDD_25") (pintype "passive"))
      (node (ref "U9") (pin "26") (pinfunction "GNDD_26") (pintype "passive"))
    )
    (net (code "21") (name "Net-(D19-A)") (class "Default")
      (node (ref "D19") (pin "1") (pinfunction "A_1") (pintype "passive"))
      (node (ref "R122") (pin "1") (pinfunction "1_1") (pintype "passive"))
    )
    (net (code "22") (name "Net-(D19-K)") (class "Default")
      (node (ref "D19") (pin "2") (pinfunction "K_2") (pintype "passive"))
      (node (ref "U9") (pin "4") (pinfunction "LED1_4") (pintype "passive"))
    )
    (net (code "23") (name "Net-(D20-A)") (class "Default")
      (node (ref "D20") (pin "1") (pinfunction "A_1") (pintype "passive"))
      (node (ref "R124") (pin "1") (pinfunction "1_1") (pintype "passive"))
    )
    (net (code "24") (name "Net-(D20-K)") (class "Default")
      (node (ref "D20") (pin "2") (pinfunction "K_2") (pintype "passive"))
      (node (ref "U9") (pin "5") (pinfunction "LED2_5") (pintype "passive"))
    )
    (net (code "25") (name "Net-(D21-A)") (class "Default")
      (node (ref "D21") (pin "1") (pinfunction "A_1") (pintype "passive"))
      (node (ref "R143") (pin "1") (pinfunction "1_1") (pintype "passive"))
    )
    (net (code "26") (name "Net-(D21-K)") (class "Default")
      (node (ref "D21") (pin "2") (pinfunction "K_2") (pintype "passive"))
      (node (ref "U10") (pin "5") (pinfunction "LED2_5") (pintype "passive"))
    )
    (net (code "27") (name "Net-(D22-A)") (class "Default")
      (node (ref "D22") (pin "1") (pinfunction "A_1") (pintype "passive"))
      (node (ref "R142") (pin "1") (pinfunction "1_1") (pintype "passive"))
    )
    (net (code "28") (name "Net-(D22-K)") (class "Default")
      (node (ref "D22") (pin "2") (pinfunction "K_2") (pintype "passive"))
      (node (ref "U10") (pin "4") (pinfunction "LED1_4") (pintype "passive"))
    )
    (net (code "29") (name "Net-(L22-Pad1)") (class "Default")
      (node (ref "L22") (pin "1") (pinfunction "1_1") (pintype "passive"))
      (node (ref "P14") (pin "1") (pinfunction "1_1") (pintype "passive"))
    )
    (net (code "30") (name "Net-(L22-Pad2)") (class "Default")
      (node (ref "L22") (pin "2") (pinfunction "2_2") (pintype "passive"))
      (node (ref "R105") (pin "2") (pinfunction "2_2") (pintype "passive"))
      (node (ref "R106") (pin "2") (pinfunction "2_2") (pintype "passive"))
    )
    (net (code "31") (name "Net-(L23-Pad2)") (class "Default")
      (node (ref "L23") (pin "2") (pinfunction "2_2") (pintype "passive"))
      (node (ref "R106") (pin "1") (pinfunction "1_1") (pintype "passive"))
      (node (ref "R107") (pin "2") (pinfunction "2_2") (pintype "passive"))
    )
    (net (code "32") (name "Net-(L25-Pad1)") (class "Default")
      (node (ref "L25") (pin "1") (pinfunction "1_1") (pintype "passive"))
      (node (ref "P16") (pin "1") (pinfunction "1_1") (pintype "passive"))
    )
    (net (code "33") (name "Net-(L25-Pad2)") (class "Default")
      (node (ref "L25") (pin "2") (pinfunction "2_2") (pintype "passive"))
      (node (ref "R113") (pin "2") (pinfunction "2_2") (pintype "passive"))
      (node (ref "R115") (pin "2") (pinfunction "2_2") (pintype "passive"))
    )
    (net (code "34") (name "Net-(L26-Pad2)") (class "Default")
      (node (ref "L26") (pin "2") (pinfunction "2_2") (pintype "passive"))
      (node (ref "R115") (pin "1") (pinfunction "1_1") (pintype "passive"))
      (node (ref "R116") (pin "2") (pinfunction "2_2") (pintype "passive"))
    )
    (net (code "35") (name "Net-(L28-Pad1)") (class "Default")
      (node (ref "L28") (pin "1") (pinfunction "1_1") (pintype "passive"))
      (node (ref "P19") (pin "1") (pinfunction "1_1") (pintype "passive"))
    )
    (net (code "36") (name "Net-(L28-Pad2)") (class "Default")
      (node (ref "L28") (pin "2") (pinfunction "2_2") (pintype "passive"))
      (node (ref "R126") (pin "2") (pinfunction "2_2") (pintype "passive"))
      (node (ref "R128") (pin "2") (pinfunction "2_2") (pintype "passive"))
    )
    (net (code "37") (name "Net-(L29-Pad2)") (class "Default")
      (node (ref "L29") (pin "2") (pinfunction "2_2") (pintype "passive"))
      (node (ref "R128") (pin "1") (pinfunction "1_1") (pintype "passive"))
      (node (ref "R129") (pin "2") (pinfunction "2_2") (pintype "passive"))
    )
    (net (code "38") (name "Net-(L31-Pad2)") (class "Default")
      (node (ref "L31") (pin "2") (pinfunction "2_2") (pintype "passive"))
      (node (ref "R136") (pin "2") (pinfunction "2_2") (pintype "passive"))
      (node (ref "R137") (pin "2") (pinfunction "2_2") (pintype "passive"))
    )
    (net (code "39") (name "Net-(L32-Pad2)") (class "Default")
      (node (ref "L32") (pin "2") (pinfunction "2_2") (pintype "passive"))
      (node (ref "R137") (pin "1") (pinfunction "1_1") (pintype "passive"))
      (node (ref "R138") (pin "2") (pinfunction "2_2") (pintype "passive"))
    )
    (net (code "40") (name "Net-(P15-Pad2)") (class "Default")
      (node (ref "P15") (pin "2") (pinfunction "2_2") (pintype "passive"))
      (node (ref "Q9") (pin "C") (pintype "passive"))
    )
    (net (code "41") (name "Net-(P17-Pad2)") (class "Default")
      (node (ref "P17") (pin "2") (pinfunction "2_2") (pintype "passive"))
      (node (ref "Q10") (pin "C") (pintype "passive"))
    )
    (net (code "42") (name "Net-(P18-Pad2)") (class "Default")
      (node (ref "P18") (pin "2") (pinfunction "2_2") (pintype "passive"))
      (node (ref "Q11") (pin "C") (pintype "passive"))
    )
    (net (code "43") (name "Net-(P20-Pad2)") (class "Default")
      (node (ref "P20") (pin "2") (pinfunction "2_2") (pintype "passive"))
      (node (ref "Q12") (pin "C") (pintype "passive"))
    )
    (net (code "44") (name "Net-(Q9-PadB)") (class "Default")
      (node (ref "Q9") (pin "B") (pintype "passive"))
      (node (ref "R112") (pin "2") (pinfunction "2_2") (pintype "passive"))
      (node (ref "R114") (pin "2") (pinfunction "2_2") (pintype "passive"))
    )
    (net (code "45") (name "Net-(Q10-PadB)") (class "Default")
      (node (ref "Q10") (pin "B") (pintype "passive"))
      (node (ref "R121") (pin "2") (pinfunction "2_2") (pintype "passive"))
      (node (ref "R123") (pin "2") (pinfunction "2_2") (pintype "passive"))
    )
    (net (code "46") (name "Net-(Q11-PadB)") (class "Default")
      (node (ref "Q11") (pin "B") (pintype "passive"))
      (node (ref "R125") (pin "2") (pinfunction "2_2") (pintype "passive"))
      (node (ref "R127") (pin "2") (pinfunction "2_2") (pintype "passive"))
    )
    (net (code "47") (name "Net-(Q12-PadB)") (class "Default")
      (node (ref "Q12") (pin "B") (pintype "passive"))
      (node (ref "R133") (pin "2") (pinfunction "2_2") (pintype "passive"))
      (node (ref "R135") (pin "2") (pinfunction "2_2") (pintype "passive"))
    )
    (net (code "48") (name "Net-(R108-Pad1)") (class "Default")
      (node (ref "R108") (pin "1") (pinfunction "1_1") (pintype "passive"))
      (node (ref "R110") (pin "2") (pinfunction "2_2") (pintype "passive"))
    )
    (net (code "49") (name "Net-(R108-Pad2)") (class "Default")
      (node (ref "R108") (pin "2") (pinfunction "2_2") (pintype "passive"))
      (node (ref "R109") (pin "1") (pinfunction "1_1") (pintype "passive"))
    )
    (net (code "50") (name "Net-(R109-Pad2)") (class "Default")
      (node (ref "R109") (pin "2") (pinfunction "2_2") (pintype "passive"))
      (node (ref "TB7") (pin "1") (pinfunction "1_1") (pintype "passive"))
    )
    (net (code "51") (name "Net-(R117-Pad1)") (class "Default")
      (node (ref "R117") (pin "1") (pinfunction "1_1") (pintype "passive"))
      (node (ref "R119") (pin "2") (pinfunction "2_2") (pintype "passive"))
    )
    (net (code "52") (name "Net-(R117-Pad2)") (class "Default")
      (node (ref "R117") (pin "2") (pinfunction "2_2") (pintype "passive"))
      (node (ref "R118") (pin "1") (pinfunction "1_1") (pintype "passive"))
    )
    (net (code "53") (name "Net-(R118-Pad2)") (class "Default")
      (node (ref "R118") (pin "2") (pinfunction "2_2") (pintype "passive"))
      (node (ref "TB8") (pin "1") (pinfunction "1_1") (pintype "passive"))
    )
    (net (code "54") (name "Net-(R130-Pad1)") (class "Default")
      (node (ref "R130") (pin "1") (pinfunction "1_1") (pintype "passive"))
      (node (ref "R132") (pin "2") (pinfunction "2_2") (pintype "passive"))
    )
    (net (code "55") (name "Net-(R130-Pad2)") (class "Default")
      (node (ref "R130") (pin "2") (pinfunction "2_2") (pintype "passive"))
      (node (ref "R131") (pin "1") (pinfunction "1_1") (pintype "passive"))
    )
    (net (code "56") (name "Net-(R131-Pad2)") (class "Default")
      (node (ref "R131") (pin "2") (pinfunction "2_2") (pintype "passive"))
      (node (ref "TB9") (pin "1") (pinfunction "1_1") (pintype "passive"))
    )
    (net (code "57") (name "Net-(R139-Pad1)") (class "Default")
      (node (ref "R139") (pin "1") (pinfunction "1_1") (pintype "passive"))
      (node (ref "R141") (pin "2") (pinfunction "2_2") (pintype "passive"))
    )
    (net (code "58") (name "Net-(R139-Pad2)") (class "Default")
      (node (ref "R139") (pin "2") (pinfunction "2_2") (pintype "passive"))
      (node (ref "R140") (pin "1") (pinfunction "1_1") (pintype "passive"))
    )
    (net (code "59") (name "Net-(R140-Pad2)") (class "Default")
      (node (ref "R140") (pin "2") (pinfunction "2_2") (pintype "passive"))
      (node (ref "TB10") (pin "1") (pinfunction "1_1") (pintype "passive"))
    )
    (net (code "60") (name "Net-(U9-IIN1)") (class "Default")
      (node (ref "C96") (pin "1") (pintype "passive"))
      (node (ref "R107") (pin "1") (pinfunction "1_1") (pintype "passive"))
      (node (ref "U9") (pin "12") (pinfunction "IIN1_12") (pintype "passive"))
    )
    (net (code "61") (name "Net-(U9-IIN2)") (class "Default")
      (node (ref "C104") (pin "1") (pintype "passive"))
      (node (ref "R116") (pin "1") (pinfunction "1_1") (pintype "passive"))
      (node (ref "U9") (pin "14") (pinfunction "IIN2_14") (pintype "passive"))
    )
    (net (code "62") (name "Net-(U9-IIP1)") (class "Default")
      (node (ref "C96") (pin "2") (pintype "passive"))
      (node (ref "R105") (pin "1") (pinfunction "1_1") (pintype "passive"))
      (node (ref "U9") (pin "11") (pinfunction "IIP1_11") (pintype "passive"))
    )
    (net (code "63") (name "Net-(U9-IIP2)") (class "Default")
      (node (ref "C104") (pin "2") (pintype "passive"))
      (node (ref "R113") (pin "1") (pinfunction "1_1") (pintype "passive"))
      (node (ref "U9") (pin "13") (pinfunction "IIP2_13") (pintype "passive"))
    )
    (net (code "64") (name "Net-(U9-VDDA)") (class "Default")
      (node (ref "C100") (pin "2") (pintype "passive"))
      (node (ref "C102") (pin "1") (pintype "passive"))
      (node (ref "C94") (pin "1") (pinfunction "1_1") (pintype "passive"))
      (node (ref "U9") (pin "21") (pinfunction "VDDA_21") (pintype "passive"))
    )
    (net (code "65") (name "Net-(U9-VDDD)") (class "Default")
      (node (ref "C101") (pin "1") (pinfunction "1_1") (pintype "passive"))
      (node (ref "C93") (pin "1") (pintype "passive"))
      (node (ref "C98") (pin "1") (pintype "passive"))
      (node (ref "U9") (pin "27") (pinfunction "VDDD_27") (pintype "passive"))
    )
    (net (code "66") (name "Net-(U9-VIN1)") (class "Default")
      (node (ref "C103") (pin "1") (pintype "passive"))
      (node (ref "L24") (pin "2") (pinfunction "2_2") (pintype "passive"))
      (node (ref "R111") (pin "2") (pinfunction "2_2") (pintype "passive"))
      (node (ref "U9") (pin "10") (pinfunction "VIN1_10") (pintype "passive"))
    )
    (net (code "67") (name "Net-(U9-VIN2)") (class "Default")
      (node (ref "C105") (pin "2") (pintype "passive"))
      (node (ref "R119") (pin "1") (pinfunction "1_1") (pintype "passive"))
      (node (ref "R120") (pin "1") (pinfunction "1_1") (pintype "passive"))
      (node (ref "U9") (pin "15") (pinfunction "VIN2_15") (pintype "passive"))
    )
    (net (code "68") (name "Net-(U9-VIP1)") (class "Default")
      (node (ref "C103") (pin "2") (pintype "passive"))
      (node (ref "R110") (pin "1") (pinfunction "1_1") (pintype "passive"))
      (node (ref "R111") (pin "1") (pinfunction "1_1") (pintype "passive"))
      (node (ref "U9") (pin "9") (pinfunction "VIP1_9") (pintype "passive"))
    )
    (net (code "69") (name "Net-(U9-VIP2)") (class "Default")
      (node (ref "C105") (pin "1") (pintype "passive"))
      (node (ref "L27") (pin "2") (pinfunction "2_2") (pintype "passive"))
      (node (ref "R120") (pin "2") (pinfunction "2_2") (pintype "passive"))
      (node (ref "U9") (pin "16") (pinfunction "VIP2_16") (pintype "passive"))
    )
    (net (code "70") (name "Net-(U9-VREF)") (class "Default")
      (node (ref "C106") (pin "1") (pintype "passive"))
      (node (ref "C107") (pin "1") (pintype "passive"))
      (node (ref "U9") (pin "19") (pinfunction "VREF_19") (pintype "passive"))
    )
    (net (code "71") (name "Net-(U9-VREF1)") (class "Default")
      (node (ref "C108") (pin "1") (pintype "passive"))
      (node (ref "C109") (pin "1") (pintype "passive"))
      (node (ref "U9") (pin "17") (pinfunction "VREF1_17") (pintype "passive"))
    )
    (net (code "72") (name "Net-(U10-IIN1)") (class "Default")
      (node (ref "C119") (pin "1") (pintype "passive"))
      (node (ref "R129") (pin "1") (pinfunction "1_1") (pintype "passive"))
      (node (ref "U10") (pin "12") (pinfunction "IIN1_12") (pintype "passive"))
    )
    (net (code "73") (name "Net-(U10-IIN2)") (class "Default")
      (node (ref "C121") (pin "1") (pintype "passive"))
      (node (ref "R138") (pin "1") (pinfunction "1_1") (pintype "passive"))
      (node (ref "U10") (pin "14") (pinfunction "IIN2_14") (pintype "passive"))
    )
    (net (code "74") (name "Net-(U10-IIP1)") (class "Default")
      (node (ref "C119") (pin "2") (pintype "passive"))
      (node (ref "R126") (pin "1") (pinfunction "1_1") (pintype "passive"))
      (node (ref "U10") (pin "11") (pinfunction "IIP1_11") (pintype "passive"))
    )
    (net (code "75") (name "Net-(U10-IIP2)") (class "Default")
      (node (ref "C121") (pin "2") (pintype "passive"))
      (node (ref "R136") (pin "1") (pinfunction "1_1") (pintype "passive"))
      (node (ref "U10") (pin "13") (pinfunction "IIP2_13") (pintype "passive"))
    )
    (net (code "76") (name "Net-(U10-VDDA)") (class "Default")
      (node (ref "C114") (pin "1") (pinfunction "1_1") (pintype "passive"))
      (node (ref "C116") (pin "1") (pintype "passive"))
      (node (ref "C118") (pin "1") (pintype "passive"))
      (node (ref "U10") (pin "21") (pinfunction "VDDA_21") (pintype "passive"))
    )
    (net (code "77") (name "Net-(U10-VDDD)") (class "Default")
      (node (ref "C113") (pin "1") (pintype "passive"))
      (node (ref "C115") (pin "1") (pintype "passive"))
      (node (ref "C117") (pin "1") (pinfunction "1_1") (pintype "passive"))
      (node (ref "U10") (pin "27") (pinfunction "VDDD_27") (pintype "passive"))
    )
    (net (code "78") (name "Net-(U10-VIN1)") (class "Default")
      (node (ref "C120") (pin "1") (pintype "passive"))
      (node (ref "L30") (pin "2") (pinfunction "2_2") (pintype "passive"))
      (node (ref "R134") (pin "2") (pinfunction "2_2") (pintype "passive"))
      (node (ref "U10") (pin "10") (pinfunction "VIN1_10") (pintype "passive"))
    )
    (net (code "79") (name "Net-(U10-VIN2)") (class "Default")
      (node (ref "C126") (pin "2") (pintype "passive"))
      (node (ref "R141") (pin "1") (pinfunction "1_1") (pintype "passive"))
      (node (ref "R144") (pin "1") (pinfunction "1_1") (pintype "passive"))
      (node (ref "U10") (pin "15") (pinfunction "VIN2_15") (pintype "passive"))
    )
    (net (code "80") (name "Net-(U10-VIP1)") (class "Default")
      (node (ref "C120") (pin "2") (pintype "passive"))
      (node (ref "R132") (pin "1") (pinfunction "1_1") (pintype "passive"))
      (node (ref "R134") (pin "1") (pinfunction "1_1") (pintype "passive"))
      (node (ref "U10") (pin "9") (pinfunction "VIP1_9") (pintype "passive"))
    )
    (net (code "81") (name "Net-(U10-VIP2)") (class "Default")
      (node (ref "C126") (pin "1") (pintype "passive"))
      (node (ref "L33") (pin "2") (pinfunction "2_2") (pintype "passive"))
      (node (ref "R144") (pin "2") (pinfunction "2_2") (pintype "passive"))
      (node (ref "U10") (pin "16") (pinfunction "VIP2_16") (pintype "passive"))
    )
    (net (code "82") (name "Net-(U10-VREF)") (class "Default")
      (node (ref "C122") (pin "1") (pintype "passive"))
      (node (ref "C124") (pin "1") (pintype "passive"))
      (node (ref "U10") (pin "19") (pinfunction "VREF_19") (pintype "passive"))
    )
    (net (code "83") (name "Net-(U10-VREF1)") (class "Default")
      (node (ref "C123") (pin "1") (pintype "passive"))
      (node (ref "C125") (pin "1") (pintype "passive"))
      (node (ref "U10") (pin "17") (pinfunction "VREF1_17") (pintype "passive"))
    )
    (net (code "84") (name "Net-(U10-XTAL2)") (class "Default")
      (node (ref "U10") (pin "2") (pinfunction "XTAL2_2") (pintype "passive"))
      (node (ref "U9") (pin "1") (pinfunction "CLKOUT_1") (pintype "passive"))
    )
    (net (code "85") (name "VCC=3.3V") (class "Default")
      (node (ref "C110") (pin "1") (pintype "passive"))
      (node (ref "C111") (pin "1") (pinfunction "1_1") (pintype "passive"))
      (node (ref "C112") (pin "1") (pintype "passive"))
      (node (ref "C95") (pin "1") (pinfunction "1_1") (pintype "passive"))
      (node (ref "C97") (pin "1") (pintype "passive"))
      (node (ref "C99") (pin "1") (pintype "passive"))
      (node (ref "M2") (pin "10") (pinfunction "Vin_10") (pintype "passive"))
      (node (ref "R122") (pin "2") (pinfunction "2_2") (pintype "passive"))
      (node (ref "R124") (pin "2") (pinfunction "2_2") (pintype "passive"))
      (node (ref "R142") (pin "2") (pinfunction "2_2") (pintype "passive"))
      (node (ref "R143") (pin "2") (pinfunction "2_2") (pintype "passive"))
      (node (ref "U10") (pin "23") (pinfunction "VCC_23") (pintype "passive"))
      (node (ref "U9") (pin "23") (pinfunction "VCC_23") (pintype "passive"))
    )
    (net (code "86") (name "VCC=5V") (class "Default")
      (node (ref "P15") (pin "1") (pinfunction "1_1") (pintype "passive"))
      (node (ref "P17") (pin "1") (pinfunction "1_1") (pintype "passive"))
      (node (ref "P18") (pin "1") (pinfunction "1_1") (pintype "passive"))
      (node (ref "P20") (pin "1") (pinfunction "1_1") (pintype "passive"))
    )
    (net (code "87") (name "unconnected-(M2-NC-Pad9)") (class "Default")
      (node (ref "M2") (pin "9") (pinfunction "NC_9") (pintype "passive"))
    )
    (net (code "88") (name "unconnected-(U9-INT1-Pad6)") (class "Default")
      (node (ref "U9") (pin "6") (pinfunction "INT1_6") (pintype "passive"))
    )
    (net (code "89") (name "unconnected-(U9-INT2-Pad7)") (class "Default")
      (node (ref "U9") (pin "7") (pinfunction "INT2_7") (pintype "passive"))
    )
    (net (code "90") (name "unconnected-(U9-NC-Pad24)") (class "Default")
      (node (ref "U9") (pin "24") (pinfunction "NC_24") (pintype "passive"))
    )
    (net (code "91") (name "unconnected-(U9-SYN-Pad28)") (class "Default")
      (node (ref "U9") (pin "28") (pinfunction "SYN_28") (pintype "passive"))
    )
    (net (code "92") (name "unconnected-(U9-XTAL1-Pad3)") (class "Default")
      (node (ref "U9") (pin "3") (pinfunction "XTAL1_3") (pintype "passive"))
    )
    (net (code "93") (name "unconnected-(U10-CLKOUT-Pad1)") (class "Default")
      (node (ref "U10") (pin "1") (pinfunction "CLKOUT_1") (pintype "passive"))
    )
    (net (code "94") (name "unconnected-(U10-INT1-Pad6)") (class "Default")
      (node (ref "U10") (pin "6") (pinfunction "INT1_6") (pintype "passive"))
    )
    (net (code "95") (name "unconnected-(U10-INT2-Pad7)") (class "Default")
      (node (ref "U10") (pin "7") (pinfunction "INT2_7") (pintype "passive"))
    )
    (net (code "96") (name "unconnected-(U10-NC-Pad24)") (class "Default")
      (node (ref "U10") (pin "24") (pinfunction "NC_24") (pintype "passive"))
    )
    (net (code "97") (name "unconnected-(U10-SYN-Pad28)") (class "Default")
      (node (ref "U10") (pin "28") (pinfunction "SYN_28") (pintype "passive"))
    )
    (net (code "98") (name "unconnected-(U10-XTAL1-Pad3)") (class "Default")
      (node (ref "U10") (pin "3") (pinfunction "XTAL1_3") (pintype "passive"))
    )
  )
)
